# 1.net
KiCad netlist of a schematic drawn in EasyEDA
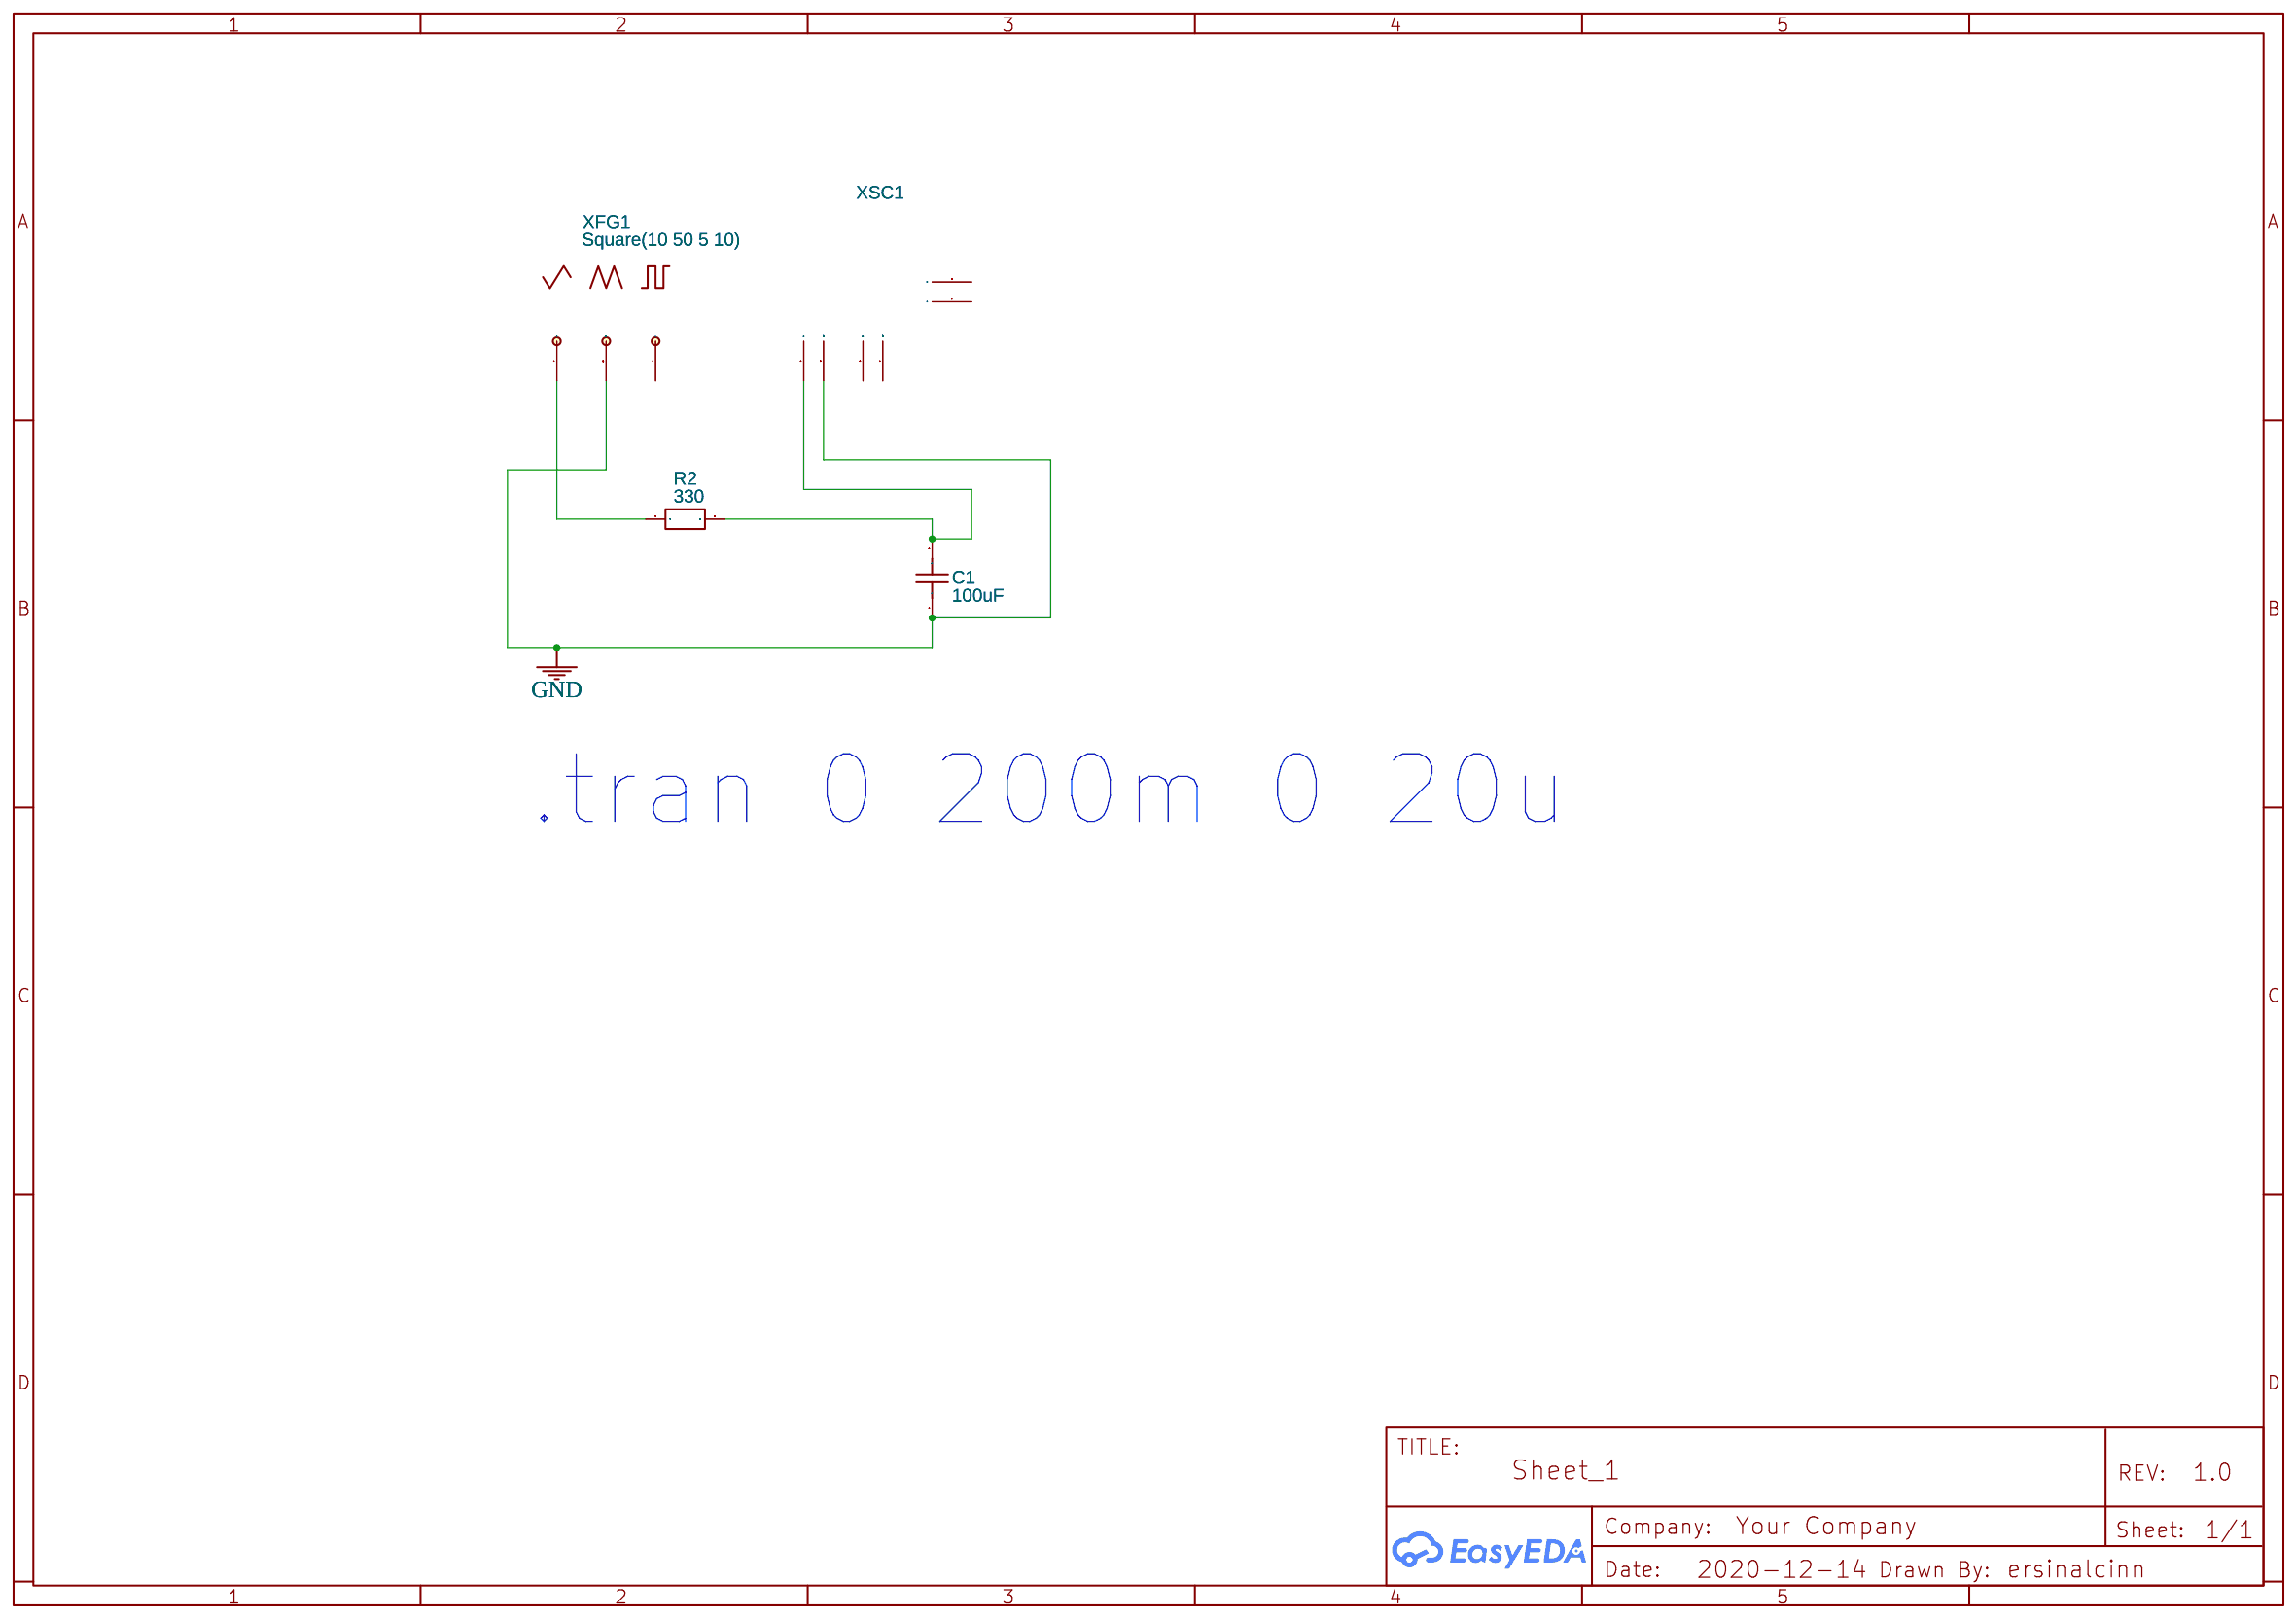
[diagram p0: schematic sheet]

(export (version "E")
  (design (tool "Eeschema 10.0.6"))
  (components
    (comp (ref "C1") (value "100uF") (libsource (lib "") (part "Capacitor_US")))
    (comp (ref "R2") (value "330") (libsource (lib "") (part "Resistor_EU")))
    (comp (ref "XFG1") (value "Square(10 50 5 10)") (libsource (lib "") (part "FUNCTIONGENERATOR")))
    (comp (ref "XSC1") (value "Oscilloscope") (libsource (lib "") (part "OSCILLOSCOPE")))
  )
  (nets
    (net (code "1") (name "GND") (class "Default")
      (node (ref "C1") (pin "1") (pinfunction "1_1") (pintype "unspecified"))
      (node (ref "XFG1") (pin "COM") (pinfunction "COM_COM") (pintype "unspecified"))
      (node (ref "XSC1") (pin "2") (pinfunction "GND1_2") (pintype "unspecified"))
    )
    (net (code "2") (name "Net-(R2-Pad1)") (class "Default")
      (node (ref "R2") (pin "1") (pinfunction "1_1") (pintype "unspecified"))
      (node (ref "XFG1") (pin "+") (pinfunction "+_+") (pintype "unspecified"))
    )
    (net (code "3") (name "Net-(XSC1-A)") (class "Default")
      (node (ref "C1") (pin "2") (pinfunction "2_2") (pintype "unspecified"))
      (node (ref "R2") (pin "2") (pinfunction "2_2") (pintype "unspecified"))
      (node (ref "XSC1") (pin "1") (pinfunction "A_1") (pintype "unspecified"))
    )
    (net (code "4") (name "unconnected-(XFG1-Pad-)") (class "Default")
      (node (ref "XFG1") (pin "-") (pinfunction "-_-") (pintype "unspecified"))
    )
    (net (code "5") (name "unconnected-(XSC1-B-Pad3)") (class "Default")
      (node (ref "XSC1") (pin "3") (pinfunction "B_3") (pintype "unspecified"))
    )
    (net (code "6") (name "unconnected-(XSC1-GND2-Pad4)") (class "Default")
      (node (ref "XSC1") (pin "4") (pinfunction "GND2_4") (pintype "unspecified"))
    )
    (net (code "7") (name "unconnected-(XSC1-T+-Pad5)") (class "Default")
      (node (ref "XSC1") (pin "5") (pinfunction "T+_5") (pintype "unspecified"))
    )
    (net (code "8") (name "unconnected-(XSC1-T--Pad6)") (class "Default")
      (node (ref "XSC1") (pin "6") (pinfunction "T-_6") (pintype "unspecified"))
    )
  )
)
